# uLI-04.net
KiCad netlist of a schematic drawn in EAGLE
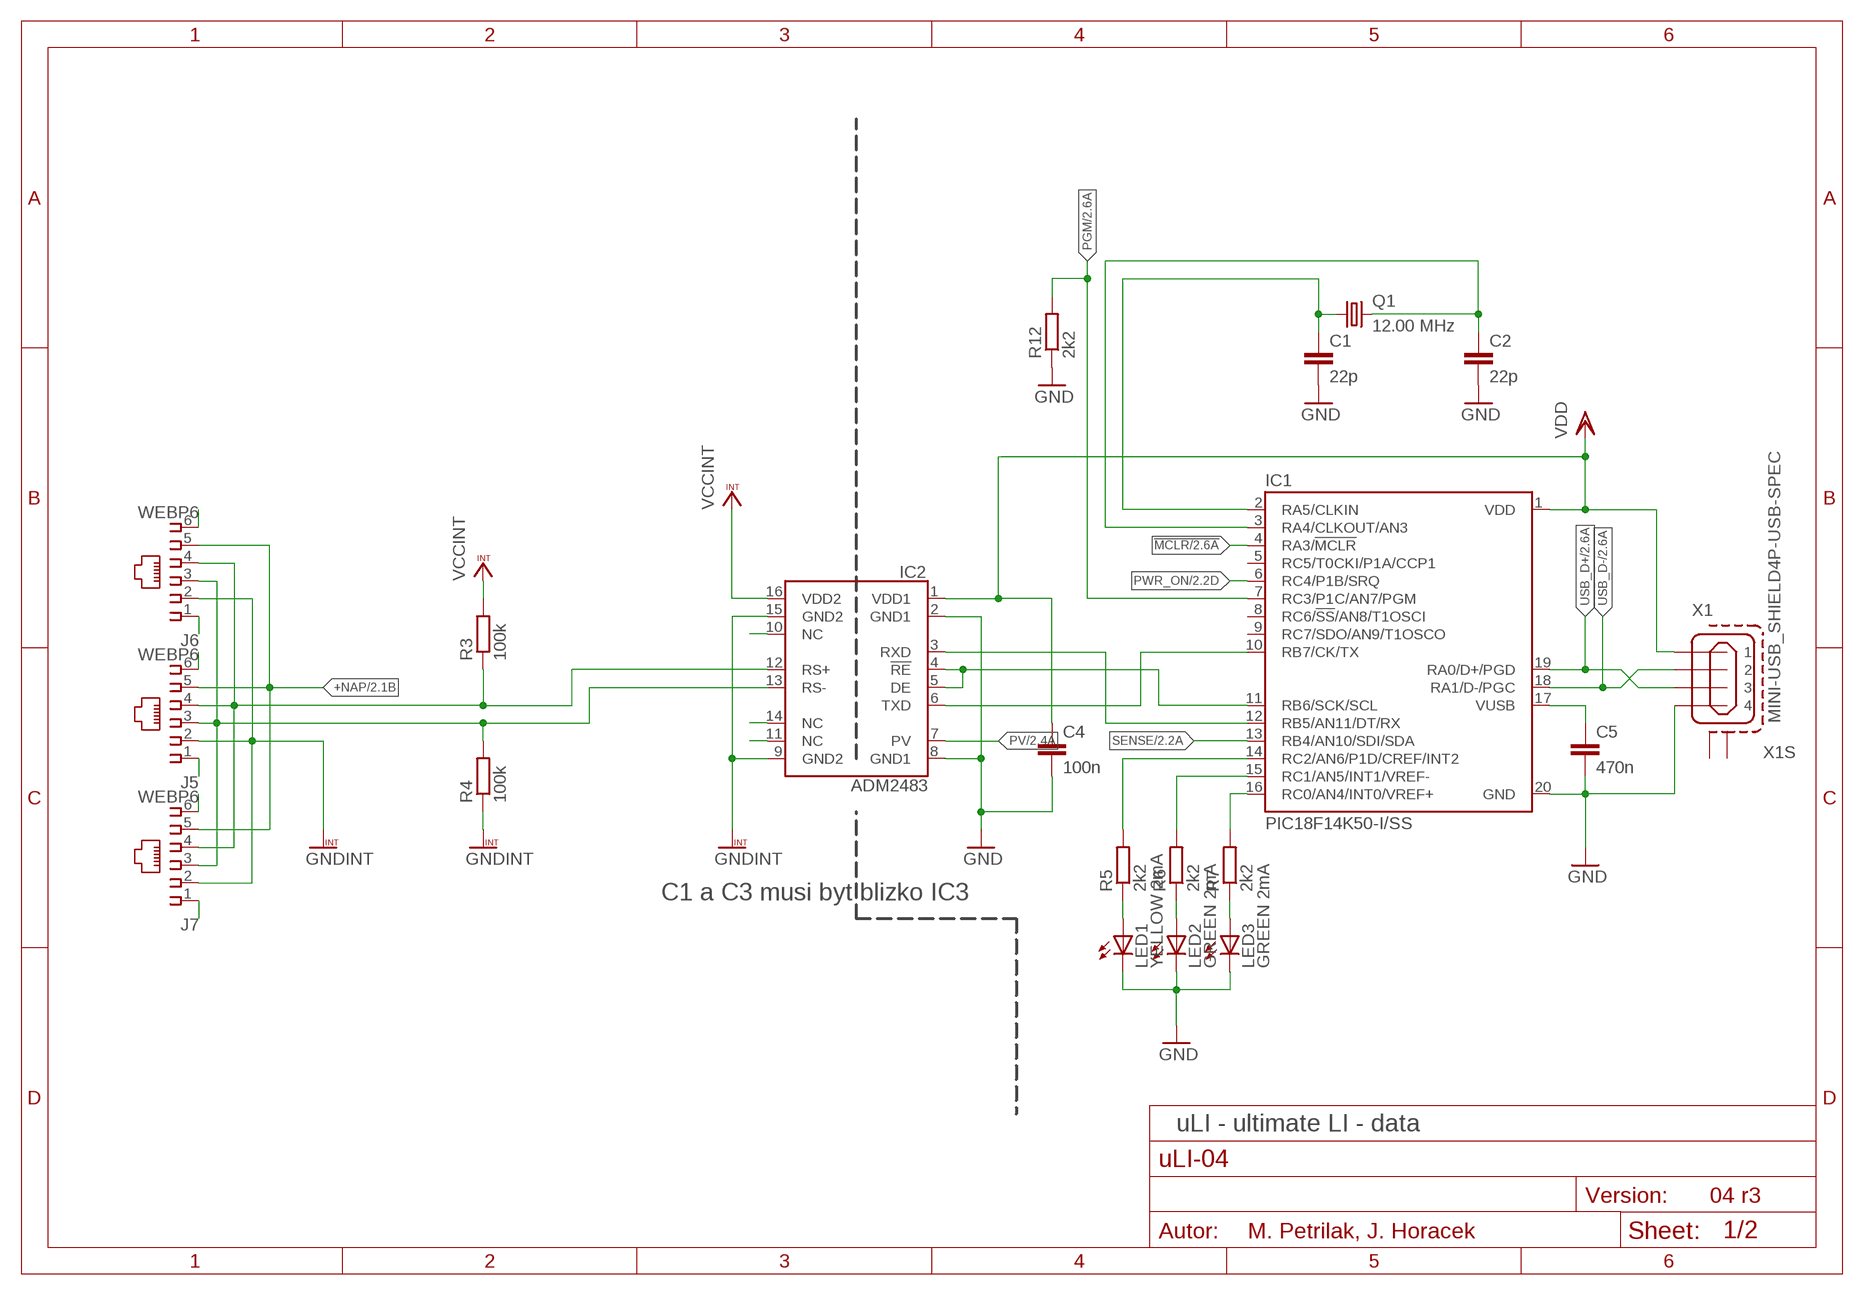
[diagram p0: schematic, sheet 1]
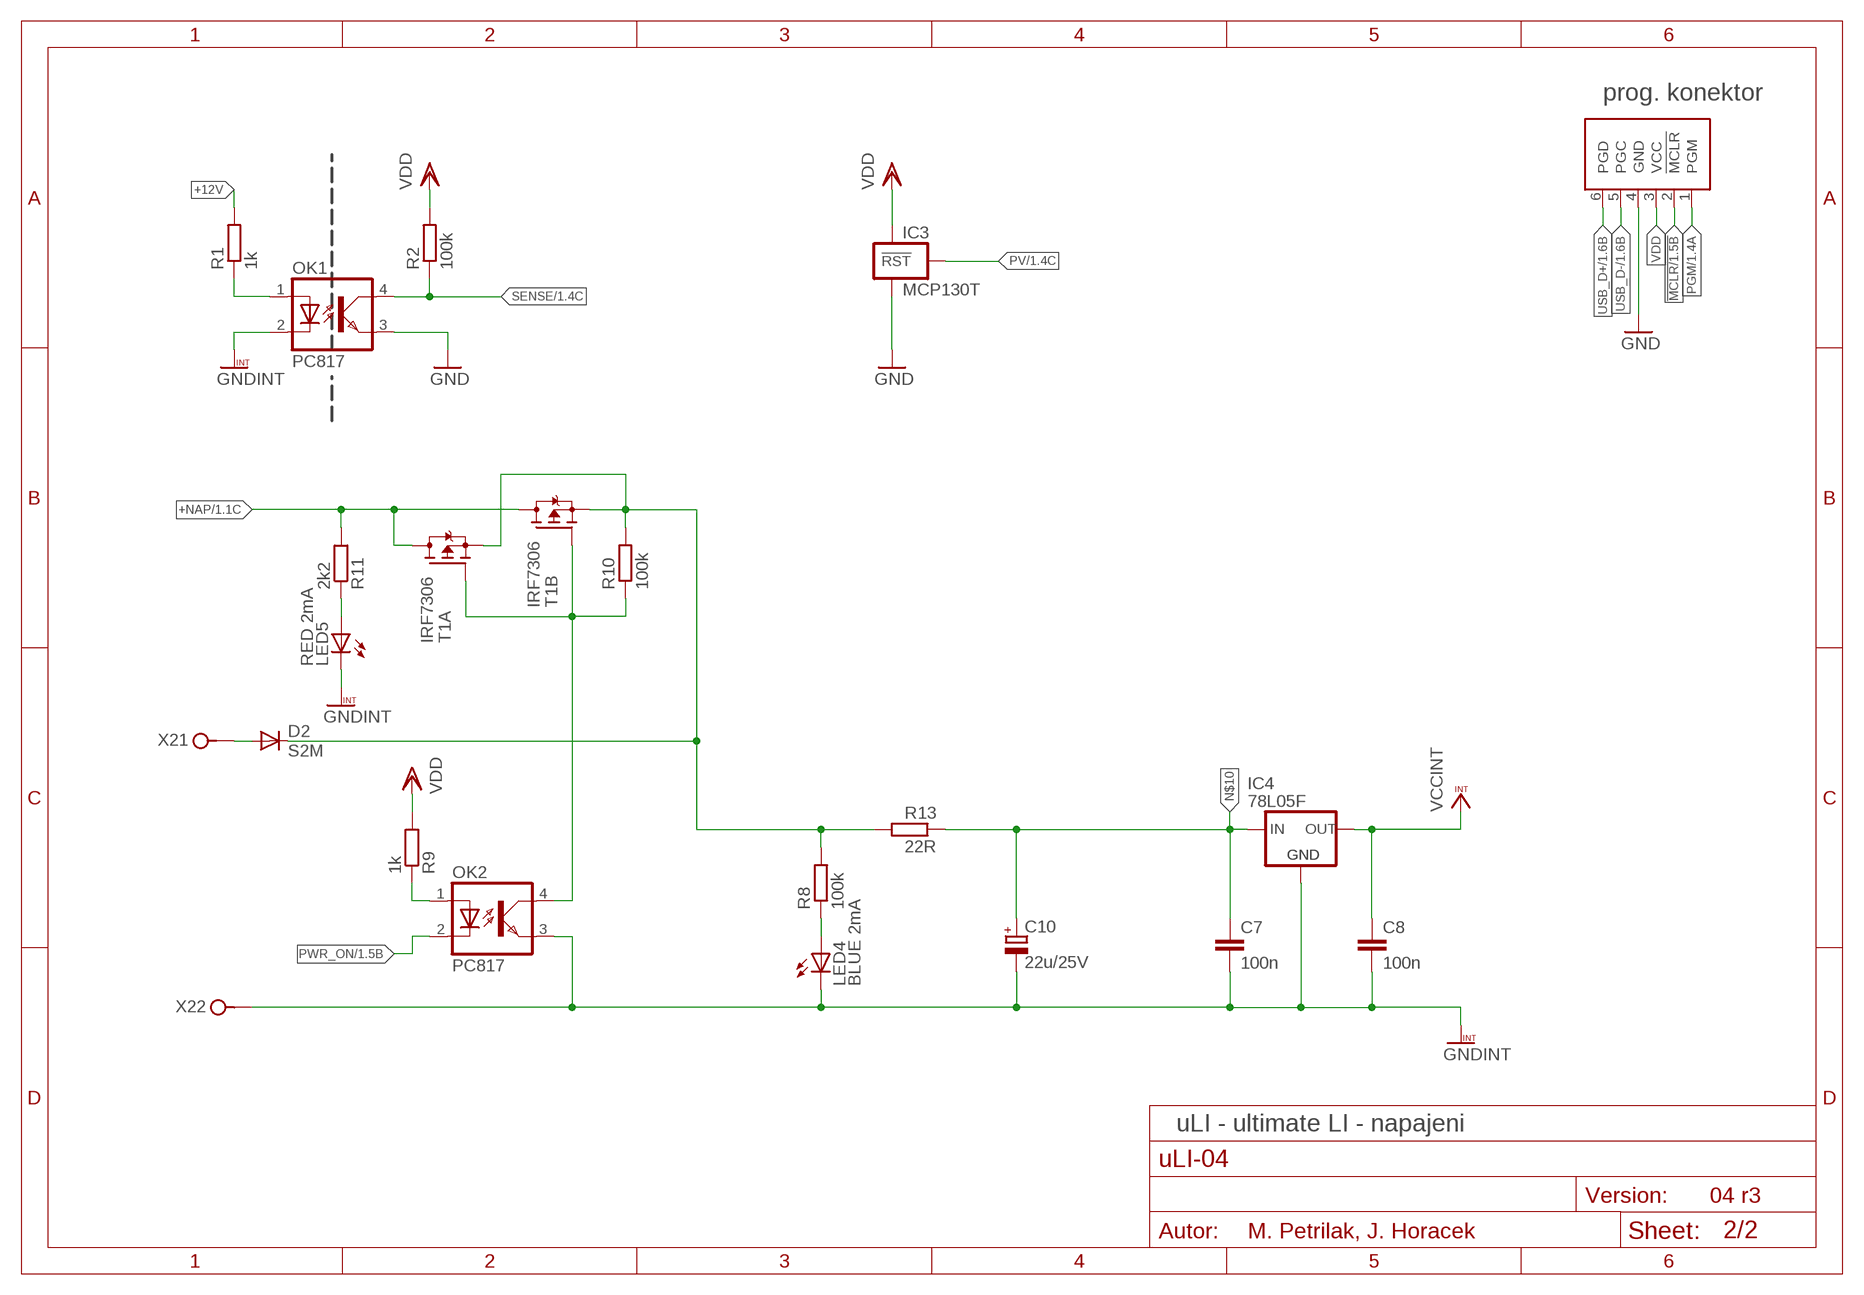
[diagram p1: schematic, sheet 2]

(export (version "E")
  (design (tool "Eeschema 10.0.6"))
  (components
    (comp (ref "C1")
      (value "22p")
      (footprint "eagle-import:C0805")
      (libsource (lib "eagle-import") (part "C-EUC0805"))
    )
    (comp (ref "C2")
      (value "22p")
      (footprint "eagle-import:C0805")
      (libsource (lib "eagle-import") (part "C-EUC0805"))
    )
    (comp (ref "C4")
      (value "100n")
      (footprint "eagle-import:C1206")
      (libsource (lib "eagle-import") (part "C-EUC1206"))
    )
    (comp (ref "C5")
      (value "470n")
      (footprint "eagle-import:C1206")
      (libsource (lib "eagle-import") (part "C-EUC1206"))
    )
    (comp (ref "IC1")
      (value "PIC18F14K50-I/SS")
      (footprint "eagle-import:SSOP20")
      (libsource (lib "eagle-import") (part "PIC18K50-I/SSF14"))
    )
    (comp (ref "IC2")
      (value "ADM2483")
      (footprint "eagle-import:SO-16W")
      (libsource (lib "eagle-import") (part "ADM2483"))
    )
    (comp (ref "J5")
      (value "WEBP6")
      (footprint "eagle-import:WEBP6-6_SPEC2")
      (libsource (lib "eagle-import") (part "WEBP6-6_SPEC2"))
    )
    (comp (ref "J6")
      (value "WEBP6")
      (footprint "eagle-import:WEBP6-6_SPEC2")
      (libsource (lib "eagle-import") (part "WEBP6-6_SPEC2"))
    )
    (comp (ref "J7")
      (value "WEBP6")
      (footprint "eagle-import:WEBP6-6_SPEC2")
      (libsource (lib "eagle-import") (part "WEBP6-6_SPEC2"))
    )
    (comp (ref "LED1")
      (value "YELLOW 2mA")
      (footprint "eagle-import:LED3MM")
      (libsource (lib "eagle-import") (part "LED3MM"))
    )
    (comp (ref "LED2")
      (value "GREEN 2mA")
      (footprint "eagle-import:LED3MM")
      (libsource (lib "eagle-import") (part "LED3MM"))
    )
    (comp (ref "LED3")
      (value "GREEN 2mA")
      (footprint "eagle-import:LED3MM")
      (libsource (lib "eagle-import") (part "LED3MM"))
    )
    (comp (ref "Q1")
      (value "12.00 MHz")
      (footprint "eagle-import:HC49U70")
      (libsource (lib "eagle-import") (part "XTAL"))
    )
    (comp (ref "R3")
      (value "100k")
      (footprint "eagle-import:R1206")
      (libsource (lib "eagle-import") (part "R-EU_R1206"))
    )
    (comp (ref "R4")
      (value "100k")
      (footprint "eagle-import:R1206")
      (libsource (lib "eagle-import") (part "R-EU_R1206"))
    )
    (comp (ref "R5")
      (value "2k2")
      (footprint "eagle-import:R1206")
      (libsource (lib "eagle-import") (part "R-EU_R1206"))
    )
    (comp (ref "R6")
      (value "2k2")
      (footprint "eagle-import:R1206")
      (libsource (lib "eagle-import") (part "R-EU_R1206"))
    )
    (comp (ref "R7")
      (value "2k2")
      (footprint "eagle-import:R1206")
      (libsource (lib "eagle-import") (part "R-EU_R1206"))
    )
    (comp (ref "R12")
      (value "2k2")
      (footprint "eagle-import:R1206")
      (libsource (lib "eagle-import") (part "R-EU_R1206"))
    )
    (comp (ref "X1")
      (value "MINI-USB_SHIELD4P-USB-SPEC")
      (footprint "eagle-import:85-32004-10X-SPEC")
      (libsource (lib "eagle-import") (part "MINI-USB_SHIELD4P-USB-SPEC"))
    )
    (comp (ref "C7")
      (value "100n")
      (footprint "eagle-import:C1206")
      (libsource (lib "eagle-import") (part "C-EUC1206"))
    )
    (comp (ref "C8")
      (value "100n")
      (footprint "eagle-import:C1206")
      (libsource (lib "eagle-import") (part "C-EUC1206"))
    )
    (comp (ref "C10")
      (value "22u/25V")
      (footprint "eagle-import:E2-5")
      (libsource (lib "eagle-import") (part "CPOL-EUE2-5"))
    )
    (comp (ref "D2")
      (value "S2M")
      (footprint "eagle-import:SMB")
      (libsource (lib "eagle-import") (part "S2M"))
    )
    (comp (ref "IC3")
      (value "MCP130T")
      (footprint "eagle-import:SOT23")
      (libsource (lib "eagle-import") (part "MCP130T"))
    )
    (comp (ref "IC4")
      (value "78L05F")
      (footprint "eagle-import:SOT89")
      (libsource (lib "eagle-import") (part "78LF05"))
    )
    (comp (ref "J1")
      (value "PICPROG2-V")
      (footprint "eagle-import:6410-06-PICPROG")
      (libsource (lib "eagle-import") (part "PICPROG2-V"))
    )
    (comp (ref "LED4")
      (value "BLUE 2mA")
      (footprint "eagle-import:LED3MM")
      (libsource (lib "eagle-import") (part "LED3MM"))
    )
    (comp (ref "LED5")
      (value "RED 2mA")
      (footprint "eagle-import:LED3MM")
      (libsource (lib "eagle-import") (part "LED3MM"))
    )
    (comp (ref "OK1")
      (value "PC817")
      (footprint "eagle-import:DIL04")
      (libsource (lib "eagle-import") (part "PC817"))
    )
    (comp (ref "OK2")
      (value "PC817")
      (footprint "eagle-import:DIL04")
      (libsource (lib "eagle-import") (part "PC817"))
    )
    (comp (ref "R1")
      (value "1k")
      (footprint "eagle-import:R1206")
      (libsource (lib "eagle-import") (part "R-EU_R1206"))
    )
    (comp (ref "R2")
      (value "100k")
      (footprint "eagle-import:R1206")
      (libsource (lib "eagle-import") (part "R-EU_R1206"))
    )
    (comp (ref "R8")
      (value "100k")
      (footprint "eagle-import:R1206")
      (libsource (lib "eagle-import") (part "R-EU_R1206"))
    )
    (comp (ref "R9")
      (value "1k")
      (footprint "eagle-import:R1206")
      (libsource (lib "eagle-import") (part "R-EU_R1206"))
    )
    (comp (ref "R10")
      (value "100k")
      (footprint "eagle-import:R1206")
      (libsource (lib "eagle-import") (part "R-EU_R1206"))
    )
    (comp (ref "R11")
      (value "2k2")
      (footprint "eagle-import:R1206")
      (libsource (lib "eagle-import") (part "R-EU_R1206"))
    )
    (comp (ref "R13")
      (value "22R")
      (footprint "eagle-import:R1206")
      (libsource (lib "eagle-import") (part "R-EU_R1206"))
    )
    (comp (ref "T1")
      (value "IRF7306")
      (footprint "eagle-import:SO08-IRF")
      (libsource (lib "eagle-import") (part "IRF7306"))
    )
    (comp (ref "X2")
      (value "ARK1550/2_S")
      (footprint "eagle-import:ARK1550_2_SPEC")
      (libsource (lib "eagle-import") (part "ARK1550/2_S"))
    )
  )
  (nets
    (net (code "1") (name "+12V") (class "Default")
      (node (ref "D2") (pin "C") (pinfunction "C_C") (pintype "passive"))
      (node (ref "R1") (pin "2") (pinfunction "2_2") (pintype "passive"))
      (node (ref "R10") (pin "2") (pinfunction "2_2") (pintype "passive"))
      (node (ref "R13") (pin "2") (pinfunction "2_2") (pintype "passive"))
      (node (ref "R8") (pin "2") (pinfunction "2_2") (pintype "passive"))
      (node (ref "T1") (pin "1") (pinfunction "S_1") (pintype "passive"))
      (node (ref "T1") (pin "3") (pinfunction "S_3") (pintype "passive"))
    )
    (net (code "2") (name "+NAP") (class "Default")
      (node (ref "J5") (pin "5") (pinfunction "5_5") (pintype "passive"))
      (node (ref "J6") (pin "5") (pinfunction "5_5") (pintype "passive"))
      (node (ref "J7") (pin "5") (pinfunction "5_5") (pintype "passive"))
      (node (ref "R11") (pin "2") (pinfunction "2_2") (pintype "passive"))
      (node (ref "T1") (pin "5") (pinfunction "D_5") (pintype "passive"))
      (node (ref "T1") (pin "6") (pinfunction "D_6") (pintype "passive"))
      (node (ref "T1") (pin "7") (pinfunction "D_7") (pintype "passive"))
      (node (ref "T1") (pin "8") (pinfunction "D_8") (pintype "passive"))
    )
    (net (code "3") (name "GND") (class "Default")
      (node (ref "C1") (pin "2") (pinfunction "2_2") (pintype "passive"))
      (node (ref "C2") (pin "2") (pinfunction "2_2") (pintype "passive"))
      (node (ref "C4") (pin "2") (pinfunction "2_2") (pintype "passive"))
      (node (ref "C5") (pin "2") (pinfunction "2_2") (pintype "passive"))
      (node (ref "IC1") (pin "20") (pinfunction "GND_20") (pintype "power_in"))
      (node (ref "IC2") (pin "2") (pinfunction "GND1_2") (pintype "power_in"))
      (node (ref "IC2") (pin "8") (pinfunction "GND1_8") (pintype "power_in"))
      (node (ref "IC3") (pin "3") (pinfunction "GND_3") (pintype "power_in"))
      (node (ref "J1") (pin "4") (pinfunction "GND_4") (pintype "power_in"))
      (node (ref "LED1") (pin "K") (pinfunction "C_K") (pintype "passive"))
      (node (ref "LED2") (pin "K") (pinfunction "C_K") (pintype "passive"))
      (node (ref "LED3") (pin "K") (pinfunction "C_K") (pintype "passive"))
      (node (ref "OK1") (pin "3") (pinfunction "EMIT_3") (pintype "passive"))
      (node (ref "R12") (pin "1") (pinfunction "1_1") (pintype "passive"))
      (node (ref "X1") (pin "4") (pinfunction "4_4") (pintype "passive"))
    )
    (net (code "4") (name "GNDINT") (class "Default")
      (node (ref "C10") (pin "-") (pinfunction "-_-") (pintype "passive"))
      (node (ref "C7") (pin "2") (pinfunction "2_2") (pintype "passive"))
      (node (ref "C8") (pin "2") (pinfunction "2_2") (pintype "passive"))
      (node (ref "IC2") (pin "15") (pinfunction "GND2_15") (pintype "power_in"))
      (node (ref "IC2") (pin "9") (pinfunction "GND2_9") (pintype "power_in"))
      (node (ref "IC4") (pin "2") (pinfunction "GND_2") (pintype "passive"))
      (node (ref "IC4") (pin "2@1") (pinfunction "GND_2@1") (pintype "passive"))
      (node (ref "J5") (pin "2") (pinfunction "2_2") (pintype "passive"))
      (node (ref "J6") (pin "2") (pinfunction "2_2") (pintype "passive"))
      (node (ref "J7") (pin "2") (pinfunction "2_2") (pintype "passive"))
      (node (ref "LED4") (pin "K") (pinfunction "C_K") (pintype "passive"))
      (node (ref "LED5") (pin "K") (pinfunction "C_K") (pintype "passive"))
      (node (ref "OK1") (pin "2") (pinfunction "C_2") (pintype "passive"))
      (node (ref "OK2") (pin "3") (pinfunction "EMIT_3") (pintype "passive"))
      (node (ref "R4") (pin "1") (pinfunction "1_1") (pintype "passive"))
      (node (ref "X2") (pin "2") (pinfunction "1_2") (pintype "passive"))
    )
    (net (code "5") (name "N$10") (class "Default")
      (node (ref "C10") (pin "+") (pinfunction "+_+") (pintype "passive"))
      (node (ref "C7") (pin "1") (pinfunction "1_1") (pintype "passive"))
      (node (ref "IC4") (pin "3") (pinfunction "VI_3") (pintype "input"))
      (node (ref "R13") (pin "1") (pinfunction "1_1") (pintype "passive"))
    )
    (net (code "6") (name "Net-(D2-PadA)") (class "Default")
      (node (ref "D2") (pin "A") (pinfunction "A_A") (pintype "passive"))
      (node (ref "X2") (pin "1") (pinfunction "1_1") (pintype "passive"))
    )
    (net (code "7") (name "Net-(IC1-RA4{slash}CLKOUT{slash}AN3)") (class "Default")
      (node (ref "C2") (pin "1") (pinfunction "1_1") (pintype "passive"))
      (node (ref "IC1") (pin "3") (pinfunction "RA4/CLKOUT/AN3_3") (pintype "bidirectional"))
      (node (ref "Q1") (pin "2") (pinfunction "2_2") (pintype "passive"))
    )
    (net (code "8") (name "Net-(IC1-RA5{slash}CLKIN)") (class "Default")
      (node (ref "C1") (pin "1") (pinfunction "1_1") (pintype "passive"))
      (node (ref "IC1") (pin "2") (pinfunction "RA5/CLKIN_2") (pintype "bidirectional"))
      (node (ref "Q1") (pin "1") (pinfunction "1_1") (pintype "passive"))
    )
    (net (code "9") (name "Net-(IC1-RB5{slash}AN11{slash}DT{slash}RX)") (class "Default")
      (node (ref "IC1") (pin "12") (pinfunction "RB5/AN11/DT/RX_12") (pintype "bidirectional"))
      (node (ref "IC2") (pin "3") (pinfunction "RXD_3") (pintype "input"))
    )
    (net (code "10") (name "Net-(IC1-RB6{slash}SCK{slash}SCL)") (class "Default")
      (node (ref "IC1") (pin "11") (pinfunction "RB6/SCK/SCL_11") (pintype "bidirectional"))
      (node (ref "IC2") (pin "4") (pinfunction "~{RE}_4") (pintype "input"))
      (node (ref "IC2") (pin "5") (pinfunction "DE_5") (pintype "input"))
    )
    (net (code "11") (name "Net-(IC1-RB7{slash}CK{slash}TX)") (class "Default")
      (node (ref "IC1") (pin "10") (pinfunction "RB7/CK/TX_10") (pintype "bidirectional"))
      (node (ref "IC2") (pin "6") (pinfunction "TXD_6") (pintype "output"))
    )
    (net (code "12") (name "Net-(IC1-RC0{slash}AN4{slash}INT0{slash}VREF+)") (class "Default")
      (node (ref "IC1") (pin "16") (pinfunction "RC0/AN4/INT0/VREF+_16") (pintype "bidirectional"))
      (node (ref "R7") (pin "2") (pinfunction "2_2") (pintype "passive"))
    )
    (net (code "13") (name "Net-(IC1-RC1{slash}AN5{slash}INT1{slash}VREF-)") (class "Default")
      (node (ref "IC1") (pin "15") (pinfunction "RC1/AN5/INT1/VREF-_15") (pintype "bidirectional"))
      (node (ref "R6") (pin "2") (pinfunction "2_2") (pintype "passive"))
    )
    (net (code "14") (name "Net-(IC1-RC2{slash}AN6{slash}P1D{slash}CREF{slash}INT2)") (class "Default")
      (node (ref "IC1") (pin "14") (pinfunction "RC2/AN6/P1D/CREF/INT2_14") (pintype "bidirectional"))
      (node (ref "R5") (pin "2") (pinfunction "2_2") (pintype "passive"))
    )
    (net (code "15") (name "Net-(IC1-VUSB)") (class "Default")
      (node (ref "C5") (pin "1") (pinfunction "1_1") (pintype "passive"))
      (node (ref "IC1") (pin "17") (pinfunction "VUSB_17") (pintype "bidirectional"))
    )
    (net (code "16") (name "Net-(IC2-RS+)") (class "Default")
      (node (ref "IC2") (pin "12") (pinfunction "RS+_12") (pintype "output"))
      (node (ref "J5") (pin "4") (pinfunction "4_4") (pintype "passive"))
      (node (ref "J6") (pin "4") (pinfunction "4_4") (pintype "passive"))
      (node (ref "J7") (pin "4") (pinfunction "4_4") (pintype "passive"))
      (node (ref "R3") (pin "1") (pinfunction "1_1") (pintype "passive"))
    )
    (net (code "17") (name "Net-(IC2-RS-)") (class "Default")
      (node (ref "IC2") (pin "13") (pinfunction "RS-_13") (pintype "output"))
      (node (ref "J5") (pin "3") (pinfunction "3_3") (pintype "passive"))
      (node (ref "J6") (pin "3") (pinfunction "3_3") (pintype "passive"))
      (node (ref "J7") (pin "3") (pinfunction "3_3") (pintype "passive"))
      (node (ref "R4") (pin "2") (pinfunction "2_2") (pintype "passive"))
    )
    (net (code "18") (name "Net-(LED1-PadA)") (class "Default")
      (node (ref "LED1") (pin "A") (pinfunction "A_A") (pintype "passive"))
      (node (ref "R5") (pin "1") (pinfunction "1_1") (pintype "passive"))
    )
    (net (code "19") (name "Net-(LED2-PadA)") (class "Default")
      (node (ref "LED2") (pin "A") (pinfunction "A_A") (pintype "passive"))
      (node (ref "R6") (pin "1") (pinfunction "1_1") (pintype "passive"))
    )
    (net (code "20") (name "Net-(LED3-PadA)") (class "Default")
      (node (ref "LED3") (pin "A") (pinfunction "A_A") (pintype "passive"))
      (node (ref "R7") (pin "1") (pinfunction "1_1") (pintype "passive"))
    )
    (net (code "21") (name "Net-(LED4-PadA)") (class "Default")
      (node (ref "LED4") (pin "A") (pinfunction "A_A") (pintype "passive"))
      (node (ref "R8") (pin "1") (pinfunction "1_1") (pintype "passive"))
    )
    (net (code "22") (name "Net-(LED5-PadA)") (class "Default")
      (node (ref "LED5") (pin "A") (pinfunction "A_A") (pintype "passive"))
      (node (ref "R11") (pin "1") (pinfunction "1_1") (pintype "passive"))
    )
    (net (code "23") (name "Net-(OK1-A)") (class "Default")
      (node (ref "OK1") (pin "1") (pinfunction "A_1") (pintype "passive"))
      (node (ref "R1") (pin "1") (pinfunction "1_1") (pintype "passive"))
    )
    (net (code "24") (name "Net-(OK2-A)") (class "Default")
      (node (ref "OK2") (pin "1") (pinfunction "A_1") (pintype "passive"))
      (node (ref "R9") (pin "1") (pinfunction "1_1") (pintype "passive"))
    )
    (net (code "25") (name "Net-(OK2-COL)") (class "Default")
      (node (ref "OK2") (pin "4") (pinfunction "COL_4") (pintype "passive"))
      (node (ref "R10") (pin "1") (pinfunction "1_1") (pintype "passive"))
      (node (ref "T1") (pin "2") (pinfunction "G_2") (pintype "passive"))
      (node (ref "T1") (pin "4") (pinfunction "G_4") (pintype "passive"))
    )
    (net (code "26") (name "PGM") (class "Default")
      (node (ref "IC1") (pin "7") (pinfunction "RC3/P1C/AN7/PGM_7") (pintype "bidirectional"))
      (node (ref "J1") (pin "1") (pinfunction "PGM_1") (pintype "output"))
      (node (ref "R12") (pin "2") (pinfunction "2_2") (pintype "passive"))
    )
    (net (code "27") (name "PV") (class "Default")
      (node (ref "IC2") (pin "7") (pinfunction "PV_7") (pintype "input"))
      (node (ref "IC3") (pin "1") (pinfunction "~{RST}_1") (pintype "output"))
    )
    (net (code "28") (name "PWR_ON") (class "Default")
      (node (ref "IC1") (pin "6") (pinfunction "RC4/P1B/SRQ_6") (pintype "bidirectional"))
      (node (ref "OK2") (pin "2") (pinfunction "C_2") (pintype "passive"))
    )
    (net (code "29") (name "SENSE") (class "Default")
      (node (ref "IC1") (pin "13") (pinfunction "RB4/AN10/SDI/SDA_13") (pintype "bidirectional"))
      (node (ref "OK1") (pin "4") (pinfunction "COL_4") (pintype "passive"))
      (node (ref "R2") (pin "1") (pinfunction "1_1") (pintype "passive"))
    )
    (net (code "30") (name "USB_D+") (class "Default")
      (node (ref "IC1") (pin "19") (pinfunction "RA0/D+/PGD_19") (pintype "bidirectional"))
      (node (ref "J1") (pin "6") (pinfunction "PGD_6") (pintype "input"))
      (node (ref "X1") (pin "3") (pinfunction "3_3") (pintype "passive"))
    )
    (net (code "31") (name "USB_D-") (class "Default")
      (node (ref "IC1") (pin "18") (pinfunction "RA1/D-/PGC_18") (pintype "bidirectional"))
      (node (ref "J1") (pin "5") (pinfunction "PGC_5") (pintype "output"))
      (node (ref "X1") (pin "2") (pinfunction "2_2") (pintype "passive"))
    )
    (net (code "32") (name "VCCINT") (class "Default")
      (node (ref "C8") (pin "1") (pinfunction "1_1") (pintype "passive"))
      (node (ref "IC2") (pin "16") (pinfunction "VDD2_16") (pintype "power_in"))
      (node (ref "IC4") (pin "1") (pinfunction "VO_1") (pintype "passive"))
      (node (ref "R3") (pin "2") (pinfunction "2_2") (pintype "passive"))
    )
    (net (code "33") (name "VDD") (class "Default")
      (node (ref "C4") (pin "1") (pinfunction "1_1") (pintype "passive"))
      (node (ref "IC1") (pin "1") (pinfunction "VDD_1") (pintype "power_in"))
      (node (ref "IC2") (pin "1") (pinfunction "VDD1_1") (pintype "power_in"))
      (node (ref "IC3") (pin "2") (pinfunction "VCC_2") (pintype "power_in"))
      (node (ref "J1") (pin "3") (pinfunction "VCC_3") (pintype "power_in"))
      (node (ref "R2") (pin "2") (pinfunction "2_2") (pintype "passive"))
      (node (ref "R9") (pin "2") (pinfunction "2_2") (pintype "passive"))
      (node (ref "X1") (pin "1") (pinfunction "1_1") (pintype "passive"))
    )
    (net (code "34") (name "unconnected-(IC1-RC5{slash}T0CKI{slash}P1A{slash}CCP1-Pad5)") (class "Default")
      (node (ref "IC1") (pin "5") (pinfunction "RC5/T0CKI/P1A/CCP1_5") (pintype "bidirectional"))
    )
    (net (code "35") (name "unconnected-(IC1-RC6{slash}~{SS}{slash}AN8{slash}T1OSCI-Pad8)") (class "Default")
      (node (ref "IC1") (pin "8") (pinfunction "RC6/~{SS}/AN8/T1OSCI_8") (pintype "bidirectional"))
    )
    (net (code "36") (name "unconnected-(IC1-RC7{slash}SDO{slash}AN9{slash}T1OSCO-Pad9)") (class "Default")
      (node (ref "IC1") (pin "9") (pinfunction "RC7/SDO/AN9/T1OSCO_9") (pintype "bidirectional"))
    )
    (net (code "37") (name "unconnected-(IC2-NC-Pad10)") (class "Default")
      (node (ref "IC2") (pin "10") (pinfunction "NC_10") (pintype "passive"))
    )
    (net (code "38") (name "unconnected-(IC2-NC-Pad11)") (class "Default")
      (node (ref "IC2") (pin "11") (pinfunction "NC_11") (pintype "passive"))
    )
    (net (code "39") (name "unconnected-(IC2-NC-Pad14)") (class "Default")
      (node (ref "IC2") (pin "14") (pinfunction "NC_14") (pintype "passive"))
    )
    (net (code "40") (name "unconnected-(J5-Pad1)") (class "Default")
      (node (ref "J5") (pin "1") (pinfunction "1_1") (pintype "passive"))
    )
    (net (code "41") (name "unconnected-(J5-Pad6)") (class "Default")
      (node (ref "J5") (pin "6") (pinfunction "6_6") (pintype "passive"))
    )
    (net (code "42") (name "unconnected-(J6-Pad1)") (class "Default")
      (node (ref "J6") (pin "1") (pinfunction "1_1") (pintype "passive"))
    )
    (net (code "43") (name "unconnected-(J6-Pad6)") (class "Default")
      (node (ref "J6") (pin "6") (pinfunction "6_6") (pintype "passive"))
    )
    (net (code "44") (name "unconnected-(J7-Pad1)") (class "Default")
      (node (ref "J7") (pin "1") (pinfunction "1_1") (pintype "passive"))
    )
    (net (code "45") (name "unconnected-(J7-Pad6)") (class "Default")
      (node (ref "J7") (pin "6") (pinfunction "6_6") (pintype "passive"))
    )
    (net (code "46") (name "unconnected-(X1B-S1-PadM1)") (class "Default")
      (node (ref "X1") (pin "M1") (pinfunction "S1_M1") (pintype "passive"))
    )
    (net (code "47") (name "unconnected-(X1B-S2-PadM2)") (class "Default")
      (node (ref "X1") (pin "M2") (pinfunction "S2_M2") (pintype "passive"))
    )
    (net (code "48") (name "~{MCLR}") (class "Default")
      (node (ref "IC1") (pin "4") (pinfunction "RA3/~{MCLR}_4") (pintype "bidirectional"))
      (node (ref "J1") (pin "2") (pinfunction "~{MCLR}_2") (pintype "output"))
    )
  )
)
